# Joystick_Module_B.net
KiCad netlist of a schematic drawn in EAGLE
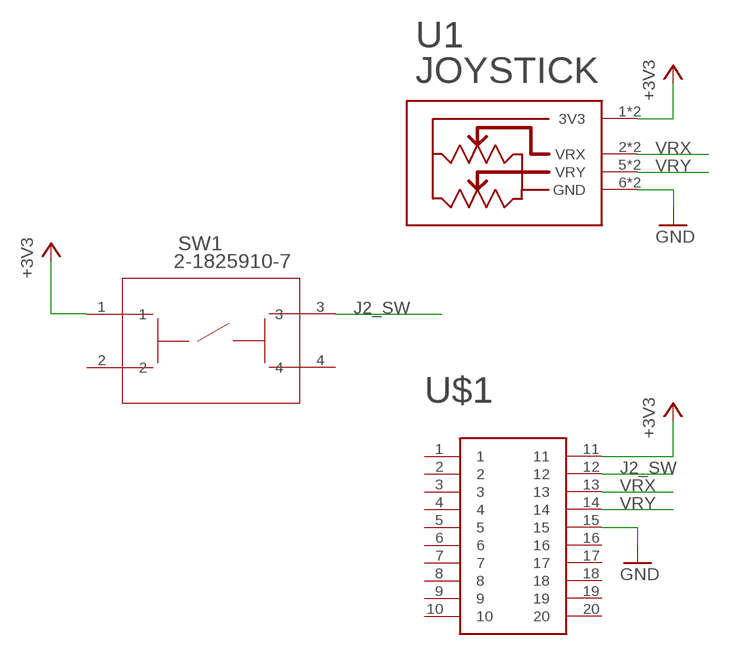
[diagram p0: schematic, sheet 1]

(export (version "E")
  (design (tool "Eeschema 10.0.6"))
  (components
    (comp (ref "SW1")
      (value "2-1825910-7")
      (footprint "eagle-import:SW4_1825910-G")
      (fields (field (name "MANUFACTURER_PART_NUMBER") "218259107"))
      (libsource (lib "eagle-import") (part "2-1825910-7"))
    )
    (comp (ref "U$1")
      (value "EDGE_CONNECTOR_20POS_CONTACTS")
      (footprint "eagle-import:EDGE_CONNECTOR_20POS_CONTACTS")
      (libsource (lib "eagle-import") (part "EDGE_CONNECTOR_20POS_CONTACTS"))
    )
    (comp (ref "U1")
      (value "27800-JOYSTICK")
      (footprint "eagle-import:27800-JOYSTICK")
      (libsource (lib "eagle-import") (part "27800-JOYSTICK"))
    )
  )
  (nets
    (net (code "1") (name "+3V3") (class "Default")
      (node (ref "SW1") (pin "1") (pinfunction "1_1") (pintype "passive"))
      (node (ref "U$1") (pin "11") (pinfunction "11_11") (pintype "bidirectional"))
      (node (ref "U1") (pin "1") (pinfunction "3V3_1") (pintype "power_in"))
      (node (ref "U1") (pin "3") (pinfunction "3V3_3") (pintype "power_in"))
    )
    (net (code "2") (name "/J2_SW") (class "Default")
      (node (ref "SW1") (pin "3") (pinfunction "3_3") (pintype "passive"))
      (node (ref "U$1") (pin "12") (pinfunction "12_12") (pintype "bidirectional"))
    )
    (net (code "3") (name "/VRX") (class "Default")
      (node (ref "U$1") (pin "13") (pinfunction "13_13") (pintype "bidirectional"))
      (node (ref "U1") (pin "2") (pinfunction "VRX_2") (pintype "bidirectional"))
      (node (ref "U1") (pin "4") (pinfunction "VRX_4") (pintype "bidirectional"))
    )
    (net (code "4") (name "/VRY") (class "Default")
      (node (ref "U$1") (pin "14") (pinfunction "14_14") (pintype "bidirectional"))
      (node (ref "U1") (pin "5") (pinfunction "VRY_5") (pintype "bidirectional"))
      (node (ref "U1") (pin "7") (pinfunction "VRY_7") (pintype "bidirectional"))
    )
    (net (code "5") (name "GND") (class "Default")
      (node (ref "U$1") (pin "15") (pinfunction "15_15") (pintype "bidirectional"))
      (node (ref "U1") (pin "6") (pinfunction "GND_6") (pintype "power_in"))
      (node (ref "U1") (pin "8") (pinfunction "GND_8") (pintype "power_in"))
    )
    (net (code "6") (name "unconnected-(SW1-Pad2)") (class "Default")
      (node (ref "SW1") (pin "2") (pinfunction "2_2") (pintype "passive"))
    )
    (net (code "7") (name "unconnected-(SW1-Pad4)") (class "Default")
      (node (ref "SW1") (pin "4") (pinfunction "4_4") (pintype "passive"))
    )
    (net (code "8") (name "unconnected-(U$1-Pad1)") (class "Default")
      (node (ref "U$1") (pin "1") (pinfunction "1_1") (pintype "bidirectional"))
    )
    (net (code "9") (name "unconnected-(U$1-Pad2)") (class "Default")
      (node (ref "U$1") (pin "2") (pinfunction "2_2") (pintype "bidirectional"))
    )
    (net (code "10") (name "unconnected-(U$1-Pad3)") (class "Default")
      (node (ref "U$1") (pin "3") (pinfunction "3_3") (pintype "bidirectional"))
    )
    (net (code "11") (name "unconnected-(U$1-Pad4)") (class "Default")
      (node (ref "U$1") (pin "4") (pinfunction "4_4") (pintype "bidirectional"))
    )
    (net (code "12") (name "unconnected-(U$1-Pad5)") (class "Default")
      (node (ref "U$1") (pin "5") (pinfunction "5_5") (pintype "bidirectional"))
    )
    (net (code "13") (name "unconnected-(U$1-Pad6)") (class "Default")
      (node (ref "U$1") (pin "6") (pinfunction "6_6") (pintype "bidirectional"))
    )
    (net (code "14") (name "unconnected-(U$1-Pad7)") (class "Default")
      (node (ref "U$1") (pin "7") (pinfunction "7_7") (pintype "bidirectional"))
    )
    (net (code "15") (name "unconnected-(U$1-Pad8)") (class "Default")
      (node (ref "U$1") (pin "8") (pinfunction "8_8") (pintype "bidirectional"))
    )
    (net (code "16") (name "unconnected-(U$1-Pad9)") (class "Default")
      (node (ref "U$1") (pin "9") (pinfunction "9_9") (pintype "bidirectional"))
    )
    (net (code "17") (name "unconnected-(U$1-Pad10)") (class "Default")
      (node (ref "U$1") (pin "10") (pinfunction "10_10") (pintype "bidirectional"))
    )
    (net (code "18") (name "unconnected-(U$1-Pad16)") (class "Default")
      (node (ref "U$1") (pin "16") (pinfunction "16_16") (pintype "bidirectional"))
    )
    (net (code "19") (name "unconnected-(U$1-Pad17)") (class "Default")
      (node (ref "U$1") (pin "17") (pinfunction "17_17") (pintype "bidirectional"))
    )
    (net (code "20") (name "unconnected-(U$1-Pad18)") (class "Default")
      (node (ref "U$1") (pin "18") (pinfunction "18_18") (pintype "bidirectional"))
    )
    (net (code "21") (name "unconnected-(U$1-Pad19)") (class "Default")
      (node (ref "U$1") (pin "19") (pinfunction "19_19") (pintype "bidirectional"))
    )
    (net (code "22") (name "unconnected-(U$1-Pad20)") (class "Default")
      (node (ref "U$1") (pin "20") (pinfunction "20_20") (pintype "bidirectional"))
    )
  )
)
